# T-Board-328_Etch_-_v0_3.net
KiCad netlist of a schematic drawn in EAGLE
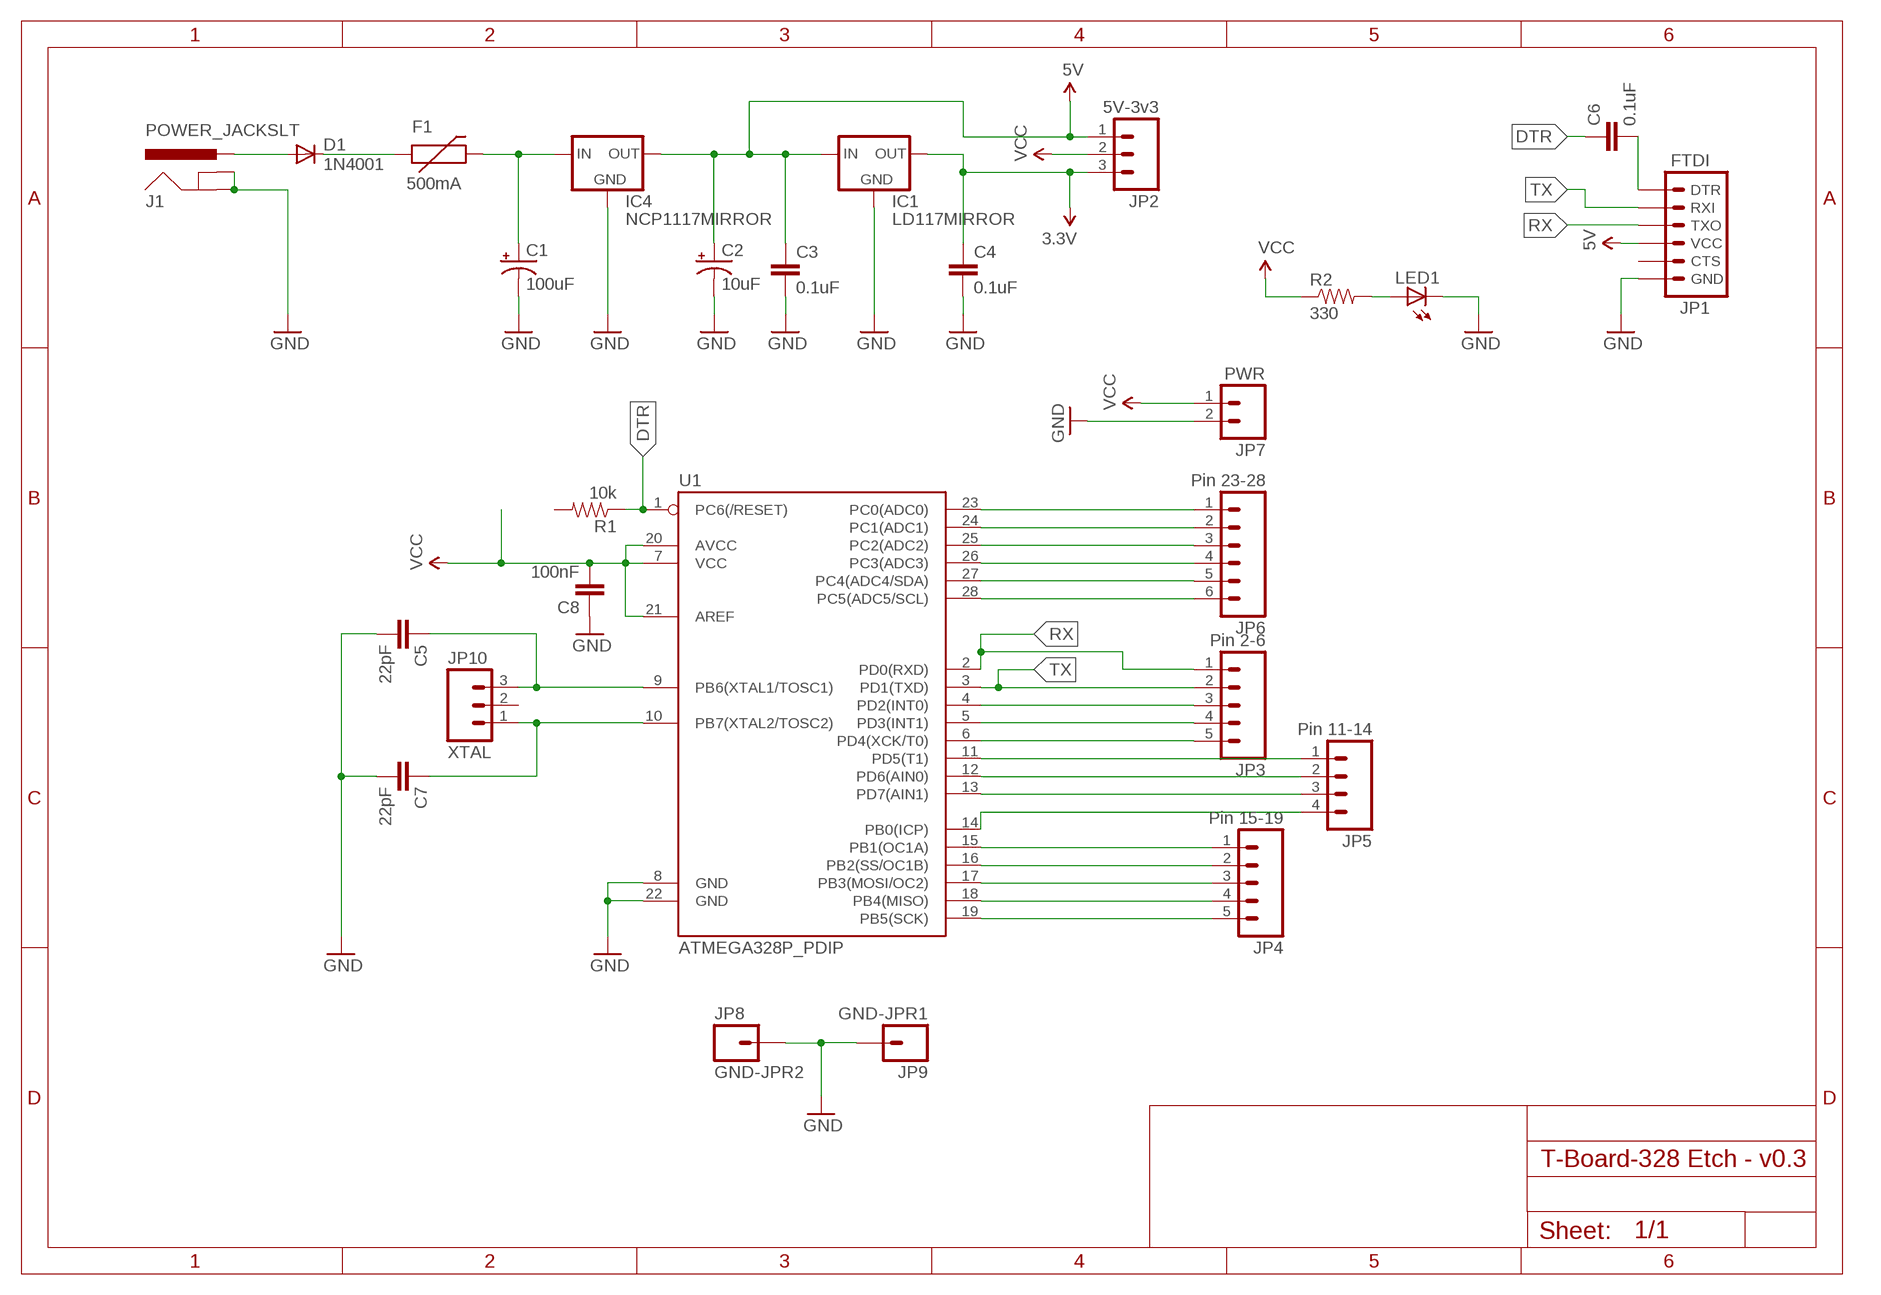
[diagram p0: schematic, sheet 1]

(export (version "E")
  (design (tool "Eeschema 10.0.6"))
  (components
    (comp (ref "C1")
      (value "100uF")
      (footprint "eagle-import:CPOL-RADIAL-100UF-25V")
      (libsource (lib "eagle-import") (part "CAP_POLPTH1"))
    )
    (comp (ref "C2")
      (value "10uF")
      (footprint "eagle-import:CPOL-RADIAL-10UF-25V")
      (libsource (lib "eagle-import") (part "CAP_POLPTH2"))
    )
    (comp (ref "C3")
      (value "0.1uF")
      (footprint "eagle-import:CAP-PTH-5MM")
      (libsource (lib "eagle-import") (part "CAPPTH1"))
    )
    (comp (ref "C4")
      (value "0.1uF")
      (footprint "eagle-import:CAP-PTH-5MM")
      (libsource (lib "eagle-import") (part "CAPPTH1"))
    )
    (comp (ref "C5")
      (value "22pF")
      (footprint "eagle-import:CAP-PTH-5MM")
      (libsource (lib "eagle-import") (part "CAPPTH1"))
    )
    (comp (ref "C6")
      (value "0.1uF")
      (footprint "eagle-import:CAP-PTH-5MM")
      (libsource (lib "eagle-import") (part "CAPPTH1"))
    )
    (comp (ref "C7")
      (value "22pF")
      (footprint "eagle-import:CAP-PTH-5MM")
      (libsource (lib "eagle-import") (part "CAPPTH1"))
    )
    (comp (ref "C8")
      (value "100nF")
      (footprint "eagle-import:CAP-PTH-5MM")
      (libsource (lib "eagle-import") (part "CAPPTH1"))
    )
    (comp (ref "D1")
      (value "1N4001")
      (footprint "eagle-import:DIODE-1N4001")
      (libsource (lib "eagle-import") (part "DIODEPTH"))
    )
    (comp (ref "F1")
      (value "500mA")
      (footprint "eagle-import:PTC")
      (libsource (lib "eagle-import") (part "PTCPTH"))
    )
    (comp (ref "IC1")
      (value "LD117MIRROR")
      (footprint "eagle-import:SOT223")
      (libsource (lib "eagle-import") (part "LD117MIRROR"))
    )
    (comp (ref "IC4")
      (value "NCP1117MIRROR")
      (footprint "eagle-import:DPACK")
      (libsource (lib "eagle-import") (part "NCP1117MIRROR"))
    )
    (comp (ref "J1")
      (value "POWER_JACKSLT")
      (footprint "eagle-import:POWER_JACK_SLOT")
      (libsource (lib "eagle-import") (part "POWER_JACKSLT"))
    )
    (comp (ref "JP1")
      (value "FTDI")
      (footprint "eagle-import:1X06_LOCK")
      (libsource (lib "eagle-import") (part "ARDUINO_SERIAL_PROGRAMLOCK"))
    )
    (comp (ref "JP2")
      (value "5V-3v3")
      (footprint "eagle-import:1X03_LOCK")
      (libsource (lib "eagle-import") (part "M03LOCK"))
    )
    (comp (ref "JP3")
      (value "Pin 2-6")
      (footprint "eagle-import:1X05_LOCK")
      (libsource (lib "eagle-import") (part "M05LOCK"))
    )
    (comp (ref "JP4")
      (value "Pin 15-19")
      (footprint "eagle-import:1X05_LOCK")
      (libsource (lib "eagle-import") (part "M05LOCK"))
    )
    (comp (ref "JP5")
      (value "Pin 11-14")
      (footprint "eagle-import:1X04_LOCK")
      (libsource (lib "eagle-import") (part "M04LOCK"))
    )
    (comp (ref "JP6")
      (value "Pin 23-28")
      (footprint "eagle-import:1X06_LOCK")
      (libsource (lib "eagle-import") (part "M06LOCK"))
    )
    (comp (ref "JP7")
      (value "PWR")
      (footprint "eagle-import:1X02_LOCK")
      (libsource (lib "eagle-import") (part "M02LOCK"))
    )
    (comp (ref "JP8")
      (value "GND-JPR2")
      (footprint "eagle-import:1X01_LONGPAD")
      (libsource (lib "eagle-import") (part "M01PTH_LONGPAD"))
    )
    (comp (ref "JP9")
      (value "GND-JPR1")
      (footprint "eagle-import:1X01_LONGPAD")
      (libsource (lib "eagle-import") (part "M01PTH_LONGPAD"))
    )
    (comp (ref "JP10")
      (value "XTAL")
      (footprint "eagle-import:1X03_LOCK")
      (libsource (lib "eagle-import") (part "M03LOCK"))
    )
    (comp (ref "LED1")
      (value "LED3MM")
      (footprint "eagle-import:LED3MM")
      (libsource (lib "eagle-import") (part "LED3MM"))
    )
    (comp (ref "R1")
      (value "10k")
      (footprint "eagle-import:1206")
      (libsource (lib "eagle-import") (part "RESISTOR1206"))
    )
    (comp (ref "R2")
      (value "330")
      (footprint "eagle-import:AXIAL-0.5")
      (libsource (lib "eagle-import") (part "RESISTORPTH-1/2W"))
    )
    (comp (ref "U1")
      (value "ATMEGA328P_PDIP")
      (footprint "eagle-import:DIL28-3")
      (libsource (lib "eagle-import") (part "ATMEGA328P_PDIP"))
    )
  )
  (nets
    (net (code "1") (name "3.3V") (class "Default")
      (node (ref "C4") (pin "1") (pinfunction "1_1") (pintype "passive"))
      (node (ref "IC1") (pin "4") (pinfunction "OUT_4") (pintype "passive"))
      (node (ref "JP2") (pin "3") (pinfunction "3_3") (pintype "passive"))
    )
    (net (code "2") (name "5V") (class "Default")
      (node (ref "C2") (pin "1") (pinfunction "+_1") (pintype "passive"))
      (node (ref "C3") (pin "1") (pinfunction "1_1") (pintype "passive"))
      (node (ref "IC1") (pin "1") (pinfunction "IN_1") (pintype "input"))
      (node (ref "IC4") (pin "4") (pinfunction "OUT_4") (pintype "passive"))
      (node (ref "JP1") (pin "4") (pinfunction "VCC_4") (pintype "passive"))
      (node (ref "JP2") (pin "1") (pinfunction "1_1") (pintype "passive"))
    )
    (net (code "3") (name "DTR") (class "Default")
      (node (ref "C6") (pin "1") (pinfunction "1_1") (pintype "passive"))
      (node (ref "R1") (pin "1") (pinfunction "1_1") (pintype "passive"))
      (node (ref "U1") (pin "1") (pinfunction "PC6(/RESET)_1") (pintype "bidirectional"))
    )
    (net (code "4") (name "GND") (class "Default")
      (node (ref "C1") (pin "2") (pinfunction "-_2") (pintype "passive"))
      (node (ref "C2") (pin "2") (pinfunction "-_2") (pintype "passive"))
      (node (ref "C3") (pin "2") (pinfunction "2_2") (pintype "passive"))
      (node (ref "C4") (pin "2") (pinfunction "2_2") (pintype "passive"))
      (node (ref "C5") (pin "2") (pinfunction "2_2") (pintype "passive"))
      (node (ref "C7") (pin "2") (pinfunction "2_2") (pintype "passive"))
      (node (ref "C8") (pin "1") (pinfunction "1_1") (pintype "passive"))
      (node (ref "IC1") (pin "3") (pinfunction "GND_3") (pintype "input"))
      (node (ref "IC4") (pin "3") (pinfunction "GND_3") (pintype "input"))
      (node (ref "J1") (pin "GND@1") (pinfunction "GNDBREAK_GND@1") (pintype "bidirectional"))
      (node (ref "J1") (pin "GND@2") (pinfunction "GND_GND@2") (pintype "bidirectional"))
      (node (ref "JP1") (pin "6") (pinfunction "GND_6") (pintype "passive"))
      (node (ref "JP7") (pin "2") (pinfunction "2_2") (pintype "passive"))
      (node (ref "JP8") (pin "1") (pinfunction "1_1") (pintype "passive"))
      (node (ref "JP9") (pin "1") (pinfunction "1_1") (pintype "passive"))
      (node (ref "LED1") (pin "K") (pinfunction "C_K") (pintype "passive"))
      (node (ref "U1") (pin "22") (pinfunction "GND_22") (pintype "bidirectional"))
      (node (ref "U1") (pin "8") (pinfunction "GND_8") (pintype "bidirectional"))
    )
    (net (code "5") (name "Net-(C1-+)") (class "Default")
      (node (ref "C1") (pin "1") (pinfunction "+_1") (pintype "passive"))
      (node (ref "F1") (pin "P$2") (pinfunction "2_P$2") (pintype "bidirectional"))
      (node (ref "IC4") (pin "1") (pinfunction "IN_1") (pintype "input"))
    )
    (net (code "6") (name "Net-(D1-PadA)") (class "Default")
      (node (ref "D1") (pin "A") (pinfunction "A_A") (pintype "passive"))
      (node (ref "J1") (pin "PWR") (pinfunction "PWR_PWR") (pintype "bidirectional"))
    )
    (net (code "7") (name "Net-(F1-1)") (class "Default")
      (node (ref "D1") (pin "C") (pinfunction "C_C") (pintype "passive"))
      (node (ref "F1") (pin "P$1") (pinfunction "1_P$1") (pintype "bidirectional"))
    )
    (net (code "8") (name "Net-(JP1-DTR)") (class "Default")
      (node (ref "C6") (pin "2") (pinfunction "2_2") (pintype "passive"))
      (node (ref "JP1") (pin "1") (pinfunction "DTR_1") (pintype "passive"))
    )
    (net (code "9") (name "Net-(R2-2)") (class "Default")
      (node (ref "LED1") (pin "A") (pinfunction "A_A") (pintype "passive"))
      (node (ref "R2") (pin "P$2") (pinfunction "2_P$2") (pintype "passive"))
    )
    (net (code "10") (name "Net-(U1-PB0(ICP))") (class "Default")
      (node (ref "JP5") (pin "4") (pinfunction "4_4") (pintype "passive"))
      (node (ref "U1") (pin "14") (pinfunction "PB0(ICP)_14") (pintype "bidirectional"))
    )
    (net (code "11") (name "Net-(U1-PB1(OC1A))") (class "Default")
      (node (ref "JP4") (pin "1") (pinfunction "1_1") (pintype "passive"))
      (node (ref "U1") (pin "15") (pinfunction "PB1(OC1A)_15") (pintype "bidirectional"))
    )
    (net (code "12") (name "Net-(U1-PB2(SS{slash}OC1B))") (class "Default")
      (node (ref "JP4") (pin "2") (pinfunction "2_2") (pintype "passive"))
      (node (ref "U1") (pin "16") (pinfunction "PB2(SS/OC1B)_16") (pintype "bidirectional"))
    )
    (net (code "13") (name "Net-(U1-PB3(MOSI{slash}OC2))") (class "Default")
      (node (ref "JP4") (pin "3") (pinfunction "3_3") (pintype "passive"))
      (node (ref "U1") (pin "17") (pinfunction "PB3(MOSI/OC2)_17") (pintype "bidirectional"))
    )
    (net (code "14") (name "Net-(U1-PB4(MISO))") (class "Default")
      (node (ref "JP4") (pin "4") (pinfunction "4_4") (pintype "passive"))
      (node (ref "U1") (pin "18") (pinfunction "PB4(MISO)_18") (pintype "bidirectional"))
    )
    (net (code "15") (name "Net-(U1-PB5(SCK))") (class "Default")
      (node (ref "JP4") (pin "5") (pinfunction "5_5") (pintype "passive"))
      (node (ref "U1") (pin "19") (pinfunction "PB5(SCK)_19") (pintype "bidirectional"))
    )
    (net (code "16") (name "Net-(U1-PB6(XTAL1{slash}TOSC1))") (class "Default")
      (node (ref "C5") (pin "1") (pinfunction "1_1") (pintype "passive"))
      (node (ref "JP10") (pin "3") (pinfunction "3_3") (pintype "passive"))
      (node (ref "U1") (pin "9") (pinfunction "PB6(XTAL1/TOSC1)_9") (pintype "bidirectional"))
    )
    (net (code "17") (name "Net-(U1-PB7(XTAL2{slash}TOSC2))") (class "Default")
      (node (ref "C7") (pin "1") (pinfunction "1_1") (pintype "passive"))
      (node (ref "JP10") (pin "1") (pinfunction "1_1") (pintype "passive"))
      (node (ref "U1") (pin "10") (pinfunction "PB7(XTAL2/TOSC2)_10") (pintype "bidirectional"))
    )
    (net (code "18") (name "Net-(U1-PC0(ADC0))") (class "Default")
      (node (ref "JP6") (pin "1") (pinfunction "1_1") (pintype "passive"))
      (node (ref "U1") (pin "23") (pinfunction "PC0(ADC0)_23") (pintype "bidirectional"))
    )
    (net (code "19") (name "Net-(U1-PC1(ADC1))") (class "Default")
      (node (ref "JP6") (pin "2") (pinfunction "2_2") (pintype "passive"))
      (node (ref "U1") (pin "24") (pinfunction "PC1(ADC1)_24") (pintype "bidirectional"))
    )
    (net (code "20") (name "Net-(U1-PC2(ADC2))") (class "Default")
      (node (ref "JP6") (pin "3") (pinfunction "3_3") (pintype "passive"))
      (node (ref "U1") (pin "25") (pinfunction "PC2(ADC2)_25") (pintype "bidirectional"))
    )
    (net (code "21") (name "Net-(U1-PC3(ADC3))") (class "Default")
      (node (ref "JP6") (pin "4") (pinfunction "4_4") (pintype "passive"))
      (node (ref "U1") (pin "26") (pinfunction "PC3(ADC3)_26") (pintype "bidirectional"))
    )
    (net (code "22") (name "Net-(U1-PC4(ADC4{slash}SDA))") (class "Default")
      (node (ref "JP6") (pin "5") (pinfunction "5_5") (pintype "passive"))
      (node (ref "U1") (pin "27") (pinfunction "PC4(ADC4/SDA)_27") (pintype "bidirectional"))
    )
    (net (code "23") (name "Net-(U1-PC5(ADC5{slash}SCL))") (class "Default")
      (node (ref "JP6") (pin "6") (pinfunction "6_6") (pintype "passive"))
      (node (ref "U1") (pin "28") (pinfunction "PC5(ADC5/SCL)_28") (pintype "bidirectional"))
    )
    (net (code "24") (name "Net-(U1-PD2(INT0))") (class "Default")
      (node (ref "JP3") (pin "3") (pinfunction "3_3") (pintype "passive"))
      (node (ref "U1") (pin "4") (pinfunction "PD2(INT0)_4") (pintype "bidirectional"))
    )
    (net (code "25") (name "Net-(U1-PD3(INT1))") (class "Default")
      (node (ref "JP3") (pin "4") (pinfunction "4_4") (pintype "passive"))
      (node (ref "U1") (pin "5") (pinfunction "PD3(INT1)_5") (pintype "bidirectional"))
    )
    (net (code "26") (name "Net-(U1-PD4(XCK{slash}T0))") (class "Default")
      (node (ref "JP3") (pin "5") (pinfunction "5_5") (pintype "passive"))
      (node (ref "U1") (pin "6") (pinfunction "PD4(XCK/T0)_6") (pintype "bidirectional"))
    )
    (net (code "27") (name "Net-(U1-PD5(T1))") (class "Default")
      (node (ref "JP5") (pin "1") (pinfunction "1_1") (pintype "passive"))
      (node (ref "U1") (pin "11") (pinfunction "PD5(T1)_11") (pintype "bidirectional"))
    )
    (net (code "28") (name "Net-(U1-PD6(AIN0))") (class "Default")
      (node (ref "JP5") (pin "2") (pinfunction "2_2") (pintype "passive"))
      (node (ref "U1") (pin "12") (pinfunction "PD6(AIN0)_12") (pintype "bidirectional"))
    )
    (net (code "29") (name "Net-(U1-PD7(AIN1))") (class "Default")
      (node (ref "JP5") (pin "3") (pinfunction "3_3") (pintype "passive"))
      (node (ref "U1") (pin "13") (pinfunction "PD7(AIN1)_13") (pintype "bidirectional"))
    )
    (net (code "30") (name "RX") (class "Default")
      (node (ref "JP1") (pin "3") (pinfunction "TXO_3") (pintype "passive"))
      (node (ref "JP3") (pin "1") (pinfunction "1_1") (pintype "passive"))
      (node (ref "U1") (pin "2") (pinfunction "PD0(RXD)_2") (pintype "bidirectional"))
    )
    (net (code "31") (name "TX") (class "Default")
      (node (ref "JP1") (pin "2") (pinfunction "RXI_2") (pintype "passive"))
      (node (ref "JP3") (pin "2") (pinfunction "2_2") (pintype "passive"))
      (node (ref "U1") (pin "3") (pinfunction "PD1(TXD)_3") (pintype "bidirectional"))
    )
    (net (code "32") (name "VCC") (class "Default")
      (node (ref "C8") (pin "2") (pinfunction "2_2") (pintype "passive"))
      (node (ref "JP2") (pin "2") (pinfunction "2_2") (pintype "passive"))
      (node (ref "JP7") (pin "1") (pinfunction "1_1") (pintype "passive"))
      (node (ref "R2") (pin "P$1") (pinfunction "1_P$1") (pintype "passive"))
      (node (ref "U1") (pin "20") (pinfunction "AVCC_20") (pintype "bidirectional"))
      (node (ref "U1") (pin "21") (pinfunction "AREF_21") (pintype "bidirectional"))
      (node (ref "U1") (pin "7") (pinfunction "VCC_7") (pintype "bidirectional"))
    )
    (net (code "33") (name "unconnected-(JP1-CTS-Pad5)") (class "Default")
      (node (ref "JP1") (pin "5") (pinfunction "CTS_5") (pintype "passive"))
    )
    (net (code "34") (name "unconnected-(JP10-Pad2)") (class "Default")
      (node (ref "JP10") (pin "2") (pinfunction "2_2") (pintype "passive"))
    )
    (net (code "35") (name "unconnected-(R1-Pad2)") (class "Default")
      (node (ref "R1") (pin "2") (pinfunction "2_2") (pintype "passive"))
    )
  )
)
